# SpaceInvaders.net
KiCad netlist of a schematic drawn in EAGLE
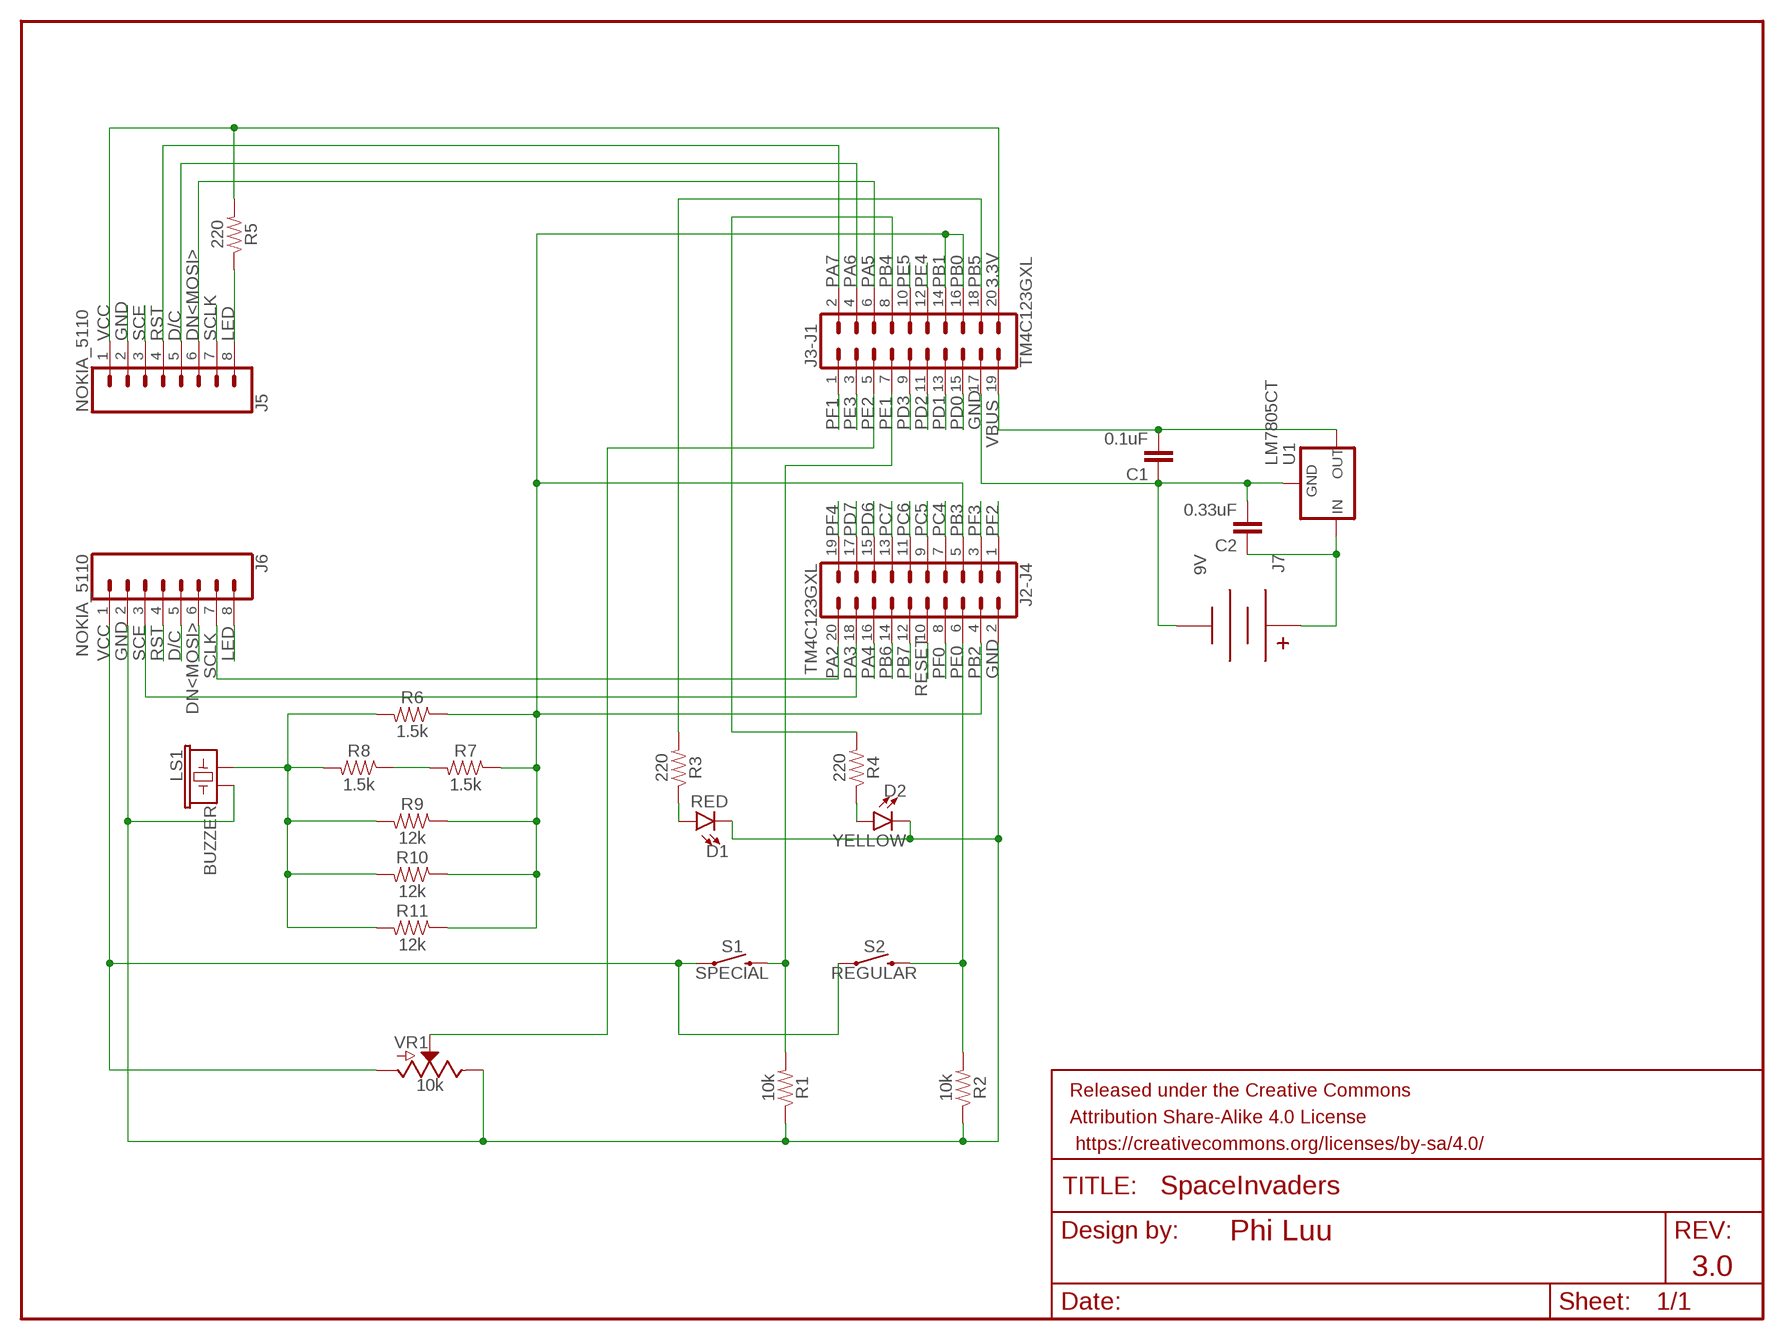
[diagram p0: schematic, sheet 1]

(export (version "E")
  (design (tool "Eeschema 10.0.6"))
  (components
    (comp (ref "C1")
      (value "0.1uF")
      (footprint "eagle-import:CAP-PTH-SMALL-KIT")
      (libsource (lib "eagle-import") (part "0.1UF-KIT-EZ-50V-20%"))
    )
    (comp (ref "C2")
      (value "0.33uF")
      (footprint "eagle-import:CAP-PTH-SMALL-KIT")
      (libsource (lib "eagle-import") (part "0.1UF-KIT-EZ-50V-20%"))
    )
    (comp (ref "D1")
      (value "RED")
      (footprint "eagle-import:LED_5MM")
      (libsource (lib "eagle-import") (part "LED5MM"))
    )
    (comp (ref "D2")
      (value "YELLOW")
      (footprint "eagle-import:LED_5MM")
      (libsource (lib "eagle-import") (part "LED5MM"))
    )
    (comp (ref "FRAME1")
      (value "FRAME-LETTER")
      (footprint "eagle-import:CREATIVE_COMMONS")
      (libsource (lib "eagle-import") (part "FRAME-LETTER"))
    )
    (comp (ref "J2-J4")
      (value "TM4C123GXL")
      (footprint "eagle-import:2X10")
      (libsource (lib "eagle-import") (part "CONN_10X2"))
    )
    (comp (ref "J3-J1")
      (value "TM4C123GXL")
      (footprint "eagle-import:2X10")
      (libsource (lib "eagle-import") (part "CONN_10X2"))
    )
    (comp (ref "J5")
      (value "NOKIA_5110")
      (footprint "eagle-import:1X08")
      (libsource (lib "eagle-import") (part "CONN_08{dblquote}"))
    )
    (comp (ref "J6")
      (value "NOKIA_5110")
      (footprint "eagle-import:1X08")
      (libsource (lib "eagle-import") (part "CONN_08{dblquote}"))
    )
    (comp (ref "J7")
      (value "9V")
      (footprint "eagle-import:BC9VPC")
      (libsource (lib "eagle-import") (part "BC9VPC"))
    )
    (comp (ref "LS1")
      (value "BUZZER")
      (footprint "eagle-import:BUZZER-12MM")
      (libsource (lib "eagle-import") (part "BUZZER-PTH"))
    )
    (comp (ref "R1")
      (value "10k")
      (footprint "eagle-import:AXIAL-0.3")
      (libsource (lib "eagle-import") (part "10KOHM-HORIZ-1/4W-5%"))
    )
    (comp (ref "R2")
      (value "10k")
      (footprint "eagle-import:AXIAL-0.3")
      (libsource (lib "eagle-import") (part "10KOHM-HORIZ-1/4W-5%"))
    )
    (comp (ref "R3")
      (value "220")
      (footprint "eagle-import:AXIAL-0.3")
      (libsource (lib "eagle-import") (part "1KOHM-HORIZ-1/4W-5%"))
    )
    (comp (ref "R4")
      (value "220")
      (footprint "eagle-import:AXIAL-0.3")
      (libsource (lib "eagle-import") (part "1KOHM-HORIZ-1/4W-5%"))
    )
    (comp (ref "R5")
      (value "220")
      (footprint "eagle-import:AXIAL-0.3")
      (libsource (lib "eagle-import") (part "1KOHM-HORIZ-1/4W-5%"))
    )
    (comp (ref "R6")
      (value "1.5k")
      (footprint "eagle-import:AXIAL-0.3")
      (libsource (lib "eagle-import") (part "1KOHM-HORIZ-1/4W-5%"))
    )
    (comp (ref "R7")
      (value "1.5k")
      (footprint "eagle-import:AXIAL-0.3")
      (libsource (lib "eagle-import") (part "1KOHM-HORIZ-1/4W-5%"))
    )
    (comp (ref "R8")
      (value "1.5k")
      (footprint "eagle-import:AXIAL-0.3")
      (libsource (lib "eagle-import") (part "1KOHM-HORIZ-1/4W-5%"))
    )
    (comp (ref "R9")
      (value "12k")
      (footprint "eagle-import:AXIAL-0.3")
      (libsource (lib "eagle-import") (part "1KOHM-HORIZ-1/4W-5%"))
    )
    (comp (ref "R10")
      (value "12k")
      (footprint "eagle-import:AXIAL-0.3")
      (libsource (lib "eagle-import") (part "1KOHM-HORIZ-1/4W-5%"))
    )
    (comp (ref "R11")
      (value "12k")
      (footprint "eagle-import:AXIAL-0.3")
      (libsource (lib "eagle-import") (part "1KOHM-HORIZ-1/4W-5%"))
    )
    (comp (ref "S1")
      (value "SPECIAL")
      (footprint "eagle-import:TACTILE_SWITCH_PTH_6.0MM")
      (libsource (lib "eagle-import") (part "MOMENTARY-SWITCH-SPST-PTH-6.0MM"))
    )
    (comp (ref "S2")
      (value "REGULAR")
      (footprint "eagle-import:TACTILE_SWITCH_PTH_6.0MM")
      (libsource (lib "eagle-import") (part "MOMENTARY-SWITCH-SPST-PTH-6.0MM"))
    )
    (comp (ref "U1")
      (value "LM7805CT")
      (footprint "eagle-import:TO-220-ALT")
      (libsource (lib "eagle-import") (part "V_REG_78XX-TO-220"))
    )
    (comp (ref "VR1")
      (value "10k")
      (footprint "eagle-import:SLIDER-MEDIUM")
      (libsource (lib "eagle-import") (part "POTENTIOMETER_SLIDE-30MM-1/10W-20%"))
    )
  )
  (nets
    (net (code "1") (name "/3.3V") (class "Default")
      (node (ref "J3-J1") (pin "20") (pinfunction "20_20") (pintype "passive"))
      (node (ref "J5") (pin "1") (pinfunction "1_1") (pintype "passive"))
      (node (ref "J6") (pin "1") (pinfunction "1_1") (pintype "passive"))
      (node (ref "R5") (pin "P$2") (pinfunction "2_P$2") (pintype "passive"))
      (node (ref "S1") (pin "1") (pinfunction "1_1") (pintype "passive"))
      (node (ref "S2") (pin "1") (pinfunction "1_1") (pintype "passive"))
      (node (ref "VR1") (pin "BOTTOM") (pinfunction "A_BOTTOM") (pintype "passive"))
    )
    (net (code "2") (name "/GND") (class "Default")
      (node (ref "C1") (pin "1") (pinfunction "1_1") (pintype "passive"))
      (node (ref "C2") (pin "2") (pinfunction "2_2") (pintype "passive"))
      (node (ref "D1") (pin "K") (pinfunction "C_K") (pintype "passive"))
      (node (ref "D2") (pin "K") (pinfunction "C_K") (pintype "passive"))
      (node (ref "J2-J4") (pin "2") (pinfunction "2_2") (pintype "passive"))
      (node (ref "J3-J1") (pin "17") (pinfunction "17_17") (pintype "passive"))
      (node (ref "J5") (pin "2") (pinfunction "2_2") (pintype "passive"))
      (node (ref "J6") (pin "2") (pinfunction "2_2") (pintype "passive"))
      (node (ref "J7") (pin "V-") (pinfunction "V-_V-") (pintype "bidirectional"))
      (node (ref "LS1") (pin "-") (pinfunction "2_-") (pintype "passive"))
      (node (ref "R1") (pin "P$1") (pinfunction "1_P$1") (pintype "passive"))
      (node (ref "R2") (pin "P$1") (pinfunction "1_P$1") (pintype "passive"))
      (node (ref "U1") (pin "GND") (pinfunction "GND_GND") (pintype "input"))
      (node (ref "VR1") (pin "TOP") (pinfunction "E_TOP") (pintype "passive"))
    )
    (net (code "3") (name "/LED") (class "Default")
      (node (ref "J5") (pin "8") (pinfunction "8_8") (pintype "passive"))
      (node (ref "J6") (pin "8") (pinfunction "8_8") (pintype "passive"))
      (node (ref "R5") (pin "P$1") (pinfunction "1_P$1") (pintype "passive"))
    )
    (net (code "4") (name "/PA2") (class "Default")
      (node (ref "J2-J4") (pin "20") (pinfunction "20_20") (pintype "passive"))
      (node (ref "J5") (pin "7") (pinfunction "7_7") (pintype "passive"))
      (node (ref "J6") (pin "7") (pinfunction "7_7") (pintype "passive"))
    )
    (net (code "5") (name "/PA3") (class "Default")
      (node (ref "J2-J4") (pin "18") (pinfunction "18_18") (pintype "passive"))
      (node (ref "J5") (pin "3") (pinfunction "3_3") (pintype "passive"))
      (node (ref "J6") (pin "3") (pinfunction "3_3") (pintype "passive"))
    )
    (net (code "6") (name "/PA4") (class "Default")
      (node (ref "J2-J4") (pin "16") (pinfunction "16_16") (pintype "passive"))
    )
    (net (code "7") (name "/PA5") (class "Default")
      (node (ref "J3-J1") (pin "6") (pinfunction "6_6") (pintype "passive"))
      (node (ref "J5") (pin "6") (pinfunction "6_6") (pintype "passive"))
      (node (ref "J6") (pin "6") (pinfunction "6_6") (pintype "passive"))
    )
    (net (code "8") (name "/PA6") (class "Default")
      (node (ref "J3-J1") (pin "4") (pinfunction "4_4") (pintype "passive"))
      (node (ref "J5") (pin "5") (pinfunction "5_5") (pintype "passive"))
      (node (ref "J6") (pin "5") (pinfunction "5_5") (pintype "passive"))
    )
    (net (code "9") (name "/PA7") (class "Default")
      (node (ref "J3-J1") (pin "2") (pinfunction "2_2") (pintype "passive"))
      (node (ref "J5") (pin "4") (pinfunction "4_4") (pintype "passive"))
      (node (ref "J6") (pin "4") (pinfunction "4_4") (pintype "passive"))
    )
    (net (code "10") (name "/PB4") (class "Default")
      (node (ref "J3-J1") (pin "8") (pinfunction "8_8") (pintype "passive"))
      (node (ref "R4") (pin "P$2") (pinfunction "2_P$2") (pintype "passive"))
    )
    (net (code "11") (name "/PB5") (class "Default")
      (node (ref "J3-J1") (pin "18") (pinfunction "18_18") (pintype "passive"))
      (node (ref "R3") (pin "P$2") (pinfunction "2_P$2") (pintype "passive"))
    )
    (net (code "12") (name "/PB6") (class "Default")
      (node (ref "J2-J4") (pin "14") (pinfunction "14_14") (pintype "passive"))
    )
    (net (code "13") (name "/PB7") (class "Default")
      (node (ref "J2-J4") (pin "12") (pinfunction "12_12") (pintype "passive"))
    )
    (net (code "14") (name "/PC4") (class "Default")
      (node (ref "J2-J4") (pin "7") (pinfunction "7_7") (pintype "passive"))
    )
    (net (code "15") (name "/PC5") (class "Default")
      (node (ref "J2-J4") (pin "9") (pinfunction "9_9") (pintype "passive"))
    )
    (net (code "16") (name "/PC6") (class "Default")
      (node (ref "J2-J4") (pin "11") (pinfunction "11_11") (pintype "passive"))
    )
    (net (code "17") (name "/PC7") (class "Default")
      (node (ref "J2-J4") (pin "13") (pinfunction "13_13") (pintype "passive"))
    )
    (net (code "18") (name "/PD0") (class "Default")
      (node (ref "J3-J1") (pin "15") (pinfunction "15_15") (pintype "passive"))
    )
    (net (code "19") (name "/PD1") (class "Default")
      (node (ref "J3-J1") (pin "13") (pinfunction "13_13") (pintype "passive"))
    )
    (net (code "20") (name "/PD2") (class "Default")
      (node (ref "J3-J1") (pin "11") (pinfunction "11_11") (pintype "passive"))
    )
    (net (code "21") (name "/PD3") (class "Default")
      (node (ref "J3-J1") (pin "9") (pinfunction "9_9") (pintype "passive"))
    )
    (net (code "22") (name "/PD6") (class "Default")
      (node (ref "J2-J4") (pin "15") (pinfunction "15_15") (pintype "passive"))
    )
    (net (code "23") (name "/PD7") (class "Default")
      (node (ref "J2-J4") (pin "17") (pinfunction "17_17") (pintype "passive"))
    )
    (net (code "24") (name "/PE0") (class "Default")
      (node (ref "J2-J4") (pin "6") (pinfunction "6_6") (pintype "passive"))
      (node (ref "R2") (pin "P$2") (pinfunction "2_P$2") (pintype "passive"))
      (node (ref "S2") (pin "3") (pinfunction "2_3") (pintype "passive"))
    )
    (net (code "25") (name "/PE1") (class "Default")
      (node (ref "J3-J1") (pin "7") (pinfunction "7_7") (pintype "passive"))
      (node (ref "R1") (pin "P$2") (pinfunction "2_P$2") (pintype "passive"))
      (node (ref "S1") (pin "3") (pinfunction "2_3") (pintype "passive"))
    )
    (net (code "26") (name "/PE2") (class "Default")
      (node (ref "J3-J1") (pin "5") (pinfunction "5_5") (pintype "passive"))
      (node (ref "VR1") (pin "WIPER") (pinfunction "S_WIPER") (pintype "passive"))
    )
    (net (code "27") (name "/PE3") (class "Default")
      (node (ref "J3-J1") (pin "3") (pinfunction "3_3") (pintype "passive"))
    )
    (net (code "28") (name "/PE4") (class "Default")
      (node (ref "J3-J1") (pin "12") (pinfunction "12_12") (pintype "passive"))
    )
    (net (code "29") (name "/PE5") (class "Default")
      (node (ref "J3-J1") (pin "10") (pinfunction "10_10") (pintype "passive"))
    )
    (net (code "30") (name "/PF0") (class "Default")
      (node (ref "J2-J4") (pin "8") (pinfunction "8_8") (pintype "passive"))
    )
    (net (code "31") (name "/PF1") (class "Default")
      (node (ref "J3-J1") (pin "1") (pinfunction "1_1") (pintype "passive"))
    )
    (net (code "32") (name "/PF2") (class "Default")
      (node (ref "J2-J4") (pin "1") (pinfunction "1_1") (pintype "passive"))
    )
    (net (code "33") (name "/PF3") (class "Default")
      (node (ref "J2-J4") (pin "3") (pinfunction "3_3") (pintype "passive"))
    )
    (net (code "34") (name "/PF4") (class "Default")
      (node (ref "J2-J4") (pin "19") (pinfunction "19_19") (pintype "passive"))
    )
    (net (code "35") (name "/RESET") (class "Default")
      (node (ref "J2-J4") (pin "10") (pinfunction "10_10") (pintype "passive"))
    )
    (net (code "36") (name "/VBUS") (class "Default")
      (node (ref "C1") (pin "2") (pinfunction "2_2") (pintype "passive"))
      (node (ref "J3-J1") (pin "19") (pinfunction "19_19") (pintype "passive"))
      (node (ref "U1") (pin "OUT") (pinfunction "OUT_OUT") (pintype "passive"))
    )
    (net (code "37") (name "Net-(C2-Pad1)") (class "Default")
      (node (ref "C2") (pin "1") (pinfunction "1_1") (pintype "passive"))
      (node (ref "J7") (pin "V+") (pinfunction "V+_V+") (pintype "bidirectional"))
      (node (ref "U1") (pin "IN") (pinfunction "IN_IN") (pintype "input"))
    )
    (net (code "38") (name "Net-(LS1-1)") (class "Default")
      (node (ref "LS1") (pin "+") (pinfunction "1_+") (pintype "passive"))
      (node (ref "R10") (pin "P$2") (pinfunction "2_P$2") (pintype "passive"))
      (node (ref "R11") (pin "P$2") (pinfunction "2_P$2") (pintype "passive"))
      (node (ref "R6") (pin "P$2") (pinfunction "2_P$2") (pintype "passive"))
      (node (ref "R8") (pin "P$2") (pinfunction "2_P$2") (pintype "passive"))
      (node (ref "R9") (pin "P$2") (pinfunction "2_P$2") (pintype "passive"))
    )
    (net (code "39") (name "Net-(R3-1)") (class "Default")
      (node (ref "D1") (pin "A") (pinfunction "A_A") (pintype "passive"))
      (node (ref "R3") (pin "P$1") (pinfunction "1_P$1") (pintype "passive"))
    )
    (net (code "40") (name "Net-(R4-1)") (class "Default")
      (node (ref "D2") (pin "A") (pinfunction "A_A") (pintype "passive"))
      (node (ref "R4") (pin "P$1") (pinfunction "1_P$1") (pintype "passive"))
    )
    (net (code "41") (name "Net-(R7-2)") (class "Default")
      (node (ref "R7") (pin "P$2") (pinfunction "2_P$2") (pintype "passive"))
      (node (ref "R8") (pin "P$1") (pinfunction "1_P$1") (pintype "passive"))
    )
    (net (code "42") (name "Net-(R10-1)") (class "Default")
      (node (ref "J2-J4") (pin "4") (pinfunction "4_4") (pintype "passive"))
      (node (ref "J2-J4") (pin "5") (pinfunction "5_5") (pintype "passive"))
      (node (ref "J3-J1") (pin "14") (pinfunction "14_14") (pintype "passive"))
      (node (ref "J3-J1") (pin "16") (pinfunction "16_16") (pintype "passive"))
      (node (ref "R10") (pin "P$1") (pinfunction "1_P$1") (pintype "passive"))
      (node (ref "R11") (pin "P$1") (pinfunction "1_P$1") (pintype "passive"))
      (node (ref "R6") (pin "P$1") (pinfunction "1_P$1") (pintype "passive"))
      (node (ref "R7") (pin "P$1") (pinfunction "1_P$1") (pintype "passive"))
      (node (ref "R9") (pin "P$1") (pinfunction "1_P$1") (pintype "passive"))
    )
  )
)
